# NUC973.net
KiCad netlist of a schematic drawn in Altium Designer
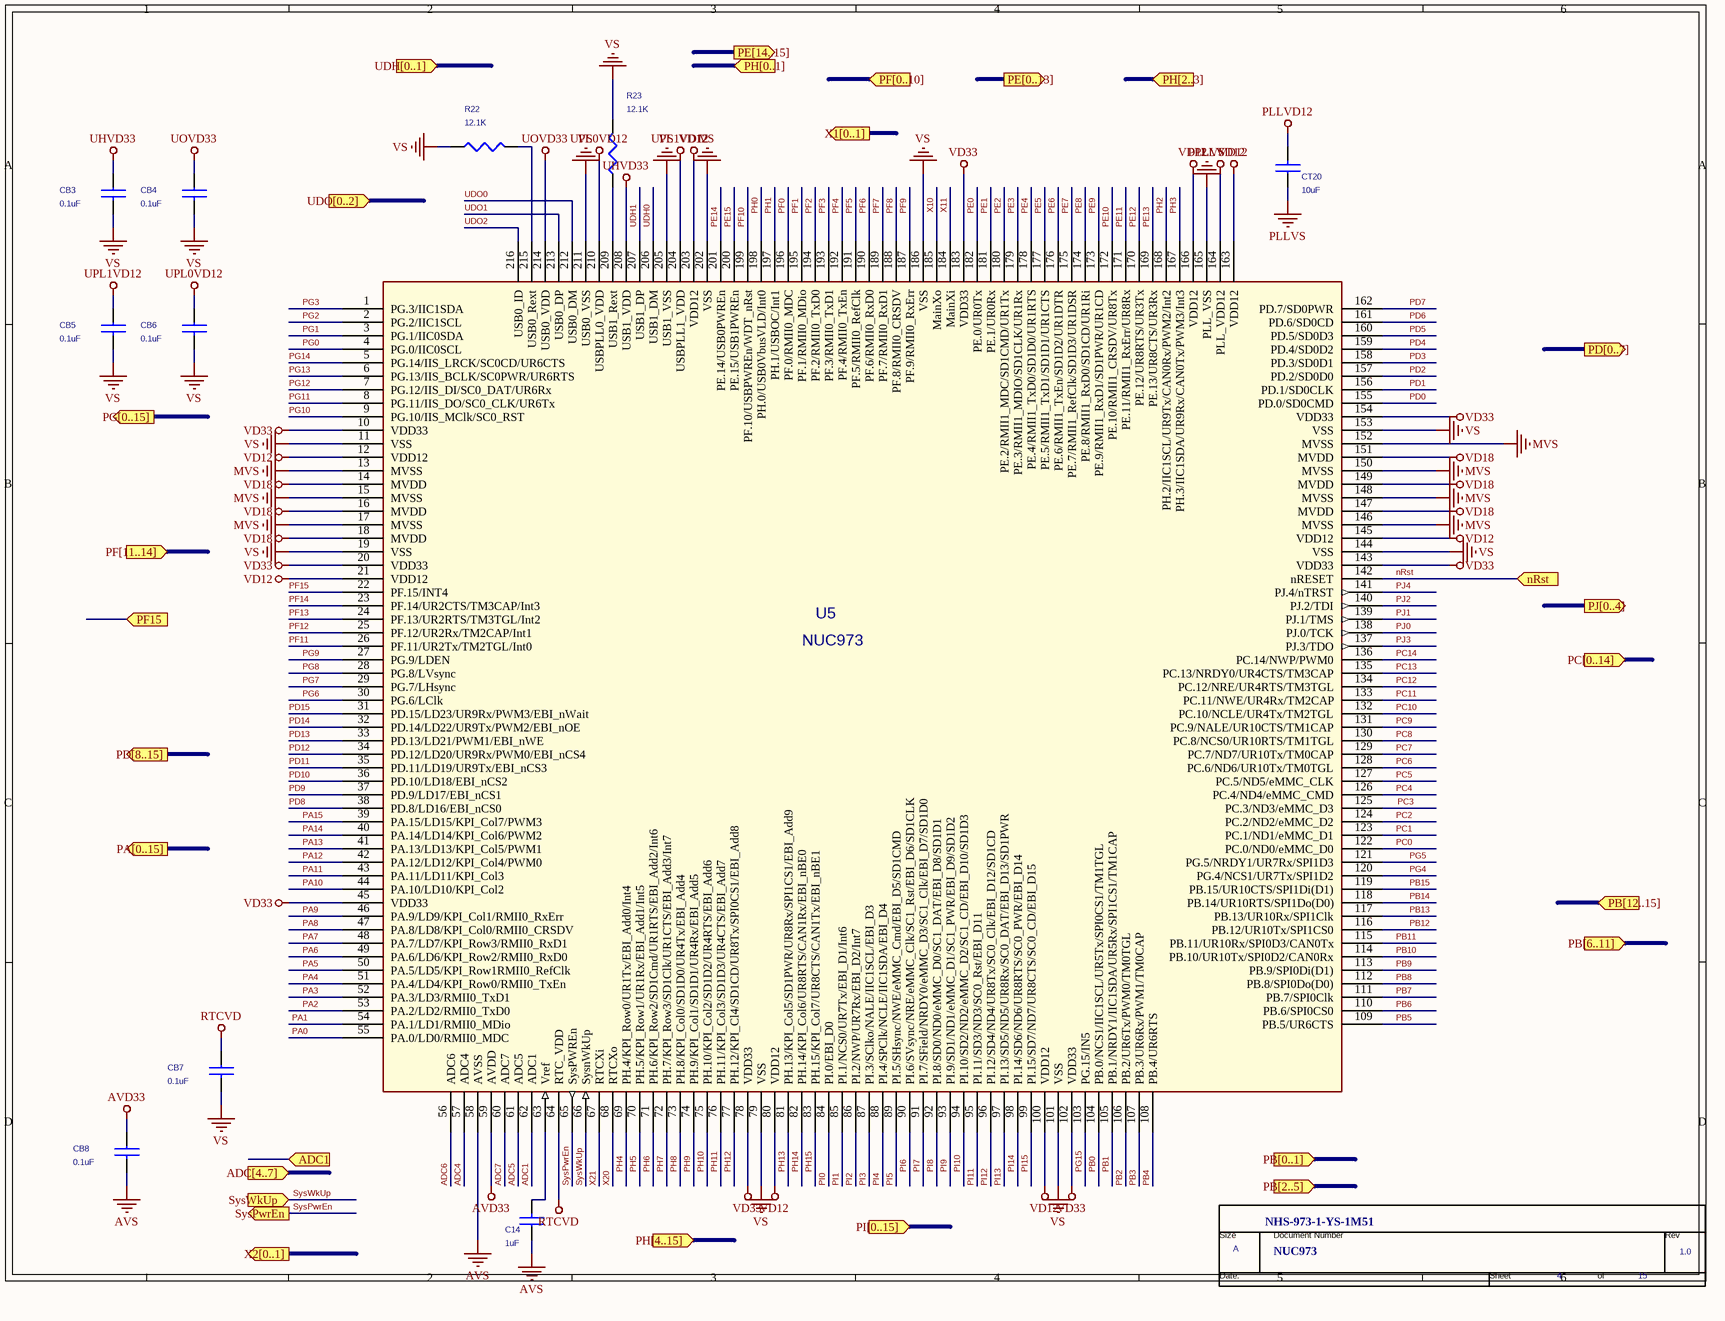
[diagram p0: NUC973.SchDoc]

(export (version "E")
  (design (tool "Eeschema 10.0.6"))
  (components
    (comp (ref "*")
      (value "TitleBlock0N")
      (fields
        (field (name "REVCODE") "1.0")
        (field (name "PAGE SIZE") "A")
        (field (name "PAGE NUMBER") "4")
        (field (name "PAGE COUNT") "15")
        (field (name "DOC") "NUC973")
        (field (name "ORGNAME") "NHS-973-1-YS-1M51")
      )
      (libsource (lib "*") (part "TitleBlock0N"))
    )
    (comp (ref "C14") (value "1uF") (footprint "C0603") (libsource (lib "*") (part "CAP NP")))
    (comp (ref "CB3") (value "0.1uF") (footprint "C0603") (libsource (lib "*") (part "CAP NP")))
    (comp (ref "CB4") (value "0.1uF") (footprint "C0603") (libsource (lib "*") (part "CAP NP")))
    (comp (ref "CB5") (value "0.1uF") (footprint "C0603") (libsource (lib "*") (part "CAP NP")))
    (comp (ref "CB6") (value "0.1uF") (footprint "C0603") (libsource (lib "*") (part "CAP NP")))
    (comp (ref "CB7") (value "0.1uF") (footprint "C0603") (libsource (lib "*") (part "CAP NP")))
    (comp (ref "CB8") (value "0.1uF") (footprint "C0603") (libsource (lib "*") (part "CAP NP")))
    (comp (ref "CT20") (value "10uF") (footprint "C0603") (libsource (lib "*") (part "CAP NP")))
    (comp (ref "R22") (value "12.1K") (footprint "R0603") (libsource (lib "*") (part "R")))
    (comp (ref "R23") (value "12.1K") (footprint "R0603") (libsource (lib "*") (part "R")))
    (comp (ref "U5") (value "NUC973") (footprint "LQFP-216") (libsource (lib "*") (part "NUC973_6")))
  )
  (nets
    (net (code "1") (name "/ADC1") (class "Default")
      (node (ref "U5") (pin "62") (pinfunction "ADC1_62") (pintype "passive"))
    )
    (net (code "2") (name "/ADC4") (class "Default")
      (node (ref "U5") (pin "57") (pinfunction "ADC4_57") (pintype "passive"))
    )
    (net (code "3") (name "/ADC5") (class "Default")
      (node (ref "U5") (pin "61") (pinfunction "ADC5_61") (pintype "passive"))
    )
    (net (code "4") (name "/ADC6") (class "Default")
      (node (ref "U5") (pin "56") (pinfunction "ADC6_56") (pintype "passive"))
    )
    (net (code "5") (name "/ADC7") (class "Default")
      (node (ref "U5") (pin "60") (pinfunction "ADC7_60") (pintype "passive"))
    )
    (net (code "7") (name "/PA0") (class "Default")
      (node (ref "U5") (pin "55") (pinfunction "PA.0/LD0/RMII0_MDC_55") (pintype "passive"))
    )
    (net (code "8") (name "/PA1") (class "Default")
      (node (ref "U5") (pin "54") (pinfunction "PA.1/LD1/RMII0_MDio_54") (pintype "passive"))
    )
    (net (code "9") (name "/PA2") (class "Default")
      (node (ref "U5") (pin "53") (pinfunction "PA.2/LD2/RMII0_TxD0_53") (pintype "passive"))
    )
    (net (code "10") (name "/PA3") (class "Default")
      (node (ref "U5") (pin "52") (pinfunction "PA.3/LD3/RMII0_TxD1_52") (pintype "passive"))
    )
    (net (code "11") (name "/PA4") (class "Default")
      (node (ref "U5") (pin "51") (pinfunction "PA.4/LD4/KPI_Row0/RMII0_TxEn_51") (pintype "passive"))
    )
    (net (code "12") (name "/PA5") (class "Default")
      (node (ref "U5") (pin "50") (pinfunction "PA.5/LD5/KPI_Row1RMII0_RefClk_50") (pintype "passive"))
    )
    (net (code "13") (name "/PA6") (class "Default")
      (node (ref "U5") (pin "49") (pinfunction "PA.6/LD6/KPI_Row2/RMII0_RxD0_49") (pintype "passive"))
    )
    (net (code "14") (name "/PA7") (class "Default")
      (node (ref "U5") (pin "48") (pinfunction "PA.7/LD7/KPI_Row3/RMII0_RxD1_48") (pintype "passive"))
    )
    (net (code "15") (name "/PA8") (class "Default")
      (node (ref "U5") (pin "47") (pinfunction "PA.8/LD8/KPI_Col0/RMII0_CRSDV_47") (pintype "passive"))
    )
    (net (code "16") (name "/PA9") (class "Default")
      (node (ref "U5") (pin "46") (pinfunction "PA.9/LD9/KPI_Col1/RMII0_RxErr_46") (pintype "passive"))
    )
    (net (code "17") (name "/PA10") (class "Default")
      (node (ref "U5") (pin "44") (pinfunction "PA.10/LD10/KPI_Col2_44") (pintype "passive"))
    )
    (net (code "18") (name "/PA11") (class "Default")
      (node (ref "U5") (pin "43") (pinfunction "PA.11/LD11/KPI_Col3_43") (pintype "passive"))
    )
    (net (code "19") (name "/PA12") (class "Default")
      (node (ref "U5") (pin "42") (pinfunction "PA.12/LD12/KPI_Col4/PWM0_42") (pintype "passive"))
    )
    (net (code "20") (name "/PA13") (class "Default")
      (node (ref "U5") (pin "41") (pinfunction "PA.13/LD13/KPI_Col5/PWM1_41") (pintype "passive"))
    )
    (net (code "21") (name "/PA14") (class "Default")
      (node (ref "U5") (pin "40") (pinfunction "PA.14/LD14/KPI_Col6/PWM2_40") (pintype "passive"))
    )
    (net (code "22") (name "/PA15") (class "Default")
      (node (ref "U5") (pin "39") (pinfunction "PA.15/LD15/KPI_Col7/PWM3_39") (pintype "passive"))
    )
    (net (code "24") (name "/PB0") (class "Default")
      (node (ref "U5") (pin "104") (pinfunction "PB.0/NCS1/IIC1SCL/UR5Tx/SPI0CS1/TM1TGL_104") (pintype "passive"))
    )
    (net (code "25") (name "/PB1") (class "Default")
      (node (ref "U5") (pin "105") (pinfunction "PB.1/NRDY1/IIC1SDA/UR5Rx/SPI1CS1/TM1CAP_105") (pintype "passive"))
    )
    (net (code "26") (name "/PB2") (class "Default")
      (node (ref "U5") (pin "106") (pinfunction "PB.2/UR6Tx/PWM0/TM0TGL_106") (pintype "passive"))
    )
    (net (code "27") (name "/PB3") (class "Default")
      (node (ref "U5") (pin "107") (pinfunction "PB.3/UR6Rx/PWM1/TM0CAP_107") (pintype "passive"))
    )
    (net (code "28") (name "/PB4") (class "Default")
      (node (ref "U5") (pin "108") (pinfunction "PB.4/UR6RTS_108") (pintype "passive"))
    )
    (net (code "29") (name "/PB5") (class "Default")
      (node (ref "U5") (pin "109") (pinfunction "PB.5/UR6CTS_109") (pintype "passive"))
    )
    (net (code "30") (name "/PB6") (class "Default")
      (node (ref "U5") (pin "110") (pinfunction "PB.6/SPI0CS0_110") (pintype "passive"))
    )
    (net (code "31") (name "/PB7") (class "Default")
      (node (ref "U5") (pin "111") (pinfunction "PB.7/SPI0Clk_111") (pintype "passive"))
    )
    (net (code "32") (name "/PB8") (class "Default")
      (node (ref "U5") (pin "112") (pinfunction "PB.8/SPI0Do(D0)_112") (pintype "passive"))
    )
    (net (code "33") (name "/PB9") (class "Default")
      (node (ref "U5") (pin "113") (pinfunction "PB.9/SPI0Di(D1)_113") (pintype "passive"))
    )
    (net (code "34") (name "/PB10") (class "Default")
      (node (ref "U5") (pin "114") (pinfunction "PB.10/UR10Tx/SPI0D2/CAN0Rx_114") (pintype "passive"))
    )
    (net (code "35") (name "/PB11") (class "Default")
      (node (ref "U5") (pin "115") (pinfunction "PB.11/UR10Rx/SPI0D3/CAN0Tx_115") (pintype "passive"))
    )
    (net (code "36") (name "/PB12") (class "Default")
      (node (ref "U5") (pin "116") (pinfunction "PB.12/UR10Tx/SPI1CS0_116") (pintype "passive"))
    )
    (net (code "37") (name "/PB13") (class "Default")
      (node (ref "U5") (pin "117") (pinfunction "PB.13/UR10Rx/SPI1Clk_117") (pintype "passive"))
    )
    (net (code "38") (name "/PB14") (class "Default")
      (node (ref "U5") (pin "118") (pinfunction "PB.14/UR10RTS/SPI1Do(D0)_118") (pintype "passive"))
    )
    (net (code "39") (name "/PB15") (class "Default")
      (node (ref "U5") (pin "119") (pinfunction "PB.15/UR10CTS/SPI1Di(D1)_119") (pintype "passive"))
    )
    (net (code "44") (name "/PC0") (class "Default")
      (node (ref "U5") (pin "122") (pinfunction "PC.0/ND0/eMMC_D0_122") (pintype "passive"))
    )
    (net (code "45") (name "/PC1") (class "Default")
      (node (ref "U5") (pin "123") (pinfunction "PC.1/ND1/eMMC_D1_123") (pintype "passive"))
    )
    (net (code "46") (name "/PC2") (class "Default")
      (node (ref "U5") (pin "124") (pinfunction "PC.2/ND2/eMMC_D2_124") (pintype "passive"))
    )
    (net (code "47") (name "/PC3") (class "Default")
      (node (ref "U5") (pin "125") (pinfunction "PC.3/ND3/eMMC_D3_125") (pintype "passive"))
    )
    (net (code "48") (name "/PC4") (class "Default")
      (node (ref "U5") (pin "126") (pinfunction "PC.4/ND4/eMMC_CMD_126") (pintype "passive"))
    )
    (net (code "49") (name "/PC5") (class "Default")
      (node (ref "U5") (pin "127") (pinfunction "PC.5/ND5/eMMC_CLK_127") (pintype "passive"))
    )
    (net (code "50") (name "/PC6") (class "Default")
      (node (ref "U5") (pin "128") (pinfunction "PC.6/ND6/UR10Tx/TM0TGL_128") (pintype "passive"))
    )
    (net (code "51") (name "/PC7") (class "Default")
      (node (ref "U5") (pin "129") (pinfunction "PC.7/ND7/UR10Tx/TM0CAP_129") (pintype "passive"))
    )
    (net (code "52") (name "/PC8") (class "Default")
      (node (ref "U5") (pin "130") (pinfunction "PC.8/NCS0/UR10RTS/TM1TGL_130") (pintype "passive"))
    )
    (net (code "53") (name "/PC9") (class "Default")
      (node (ref "U5") (pin "131") (pinfunction "PC.9/NALE/UR10CTS/TM1CAP_131") (pintype "passive"))
    )
    (net (code "54") (name "/PC10") (class "Default")
      (node (ref "U5") (pin "132") (pinfunction "PC.10/NCLE/UR4Tx/TM2TGL_132") (pintype "passive"))
    )
    (net (code "55") (name "/PC11") (class "Default")
      (node (ref "U5") (pin "133") (pinfunction "PC.11/NWE/UR4Rx/TM2CAP_133") (pintype "passive"))
    )
    (net (code "56") (name "/PC12") (class "Default")
      (node (ref "U5") (pin "134") (pinfunction "PC.12/NRE/UR4RTS/TM3TGL_134") (pintype "passive"))
    )
    (net (code "57") (name "/PC13") (class "Default")
      (node (ref "U5") (pin "135") (pinfunction "PC.13/NRDY0/UR4CTS/TM3CAP_135") (pintype "passive"))
    )
    (net (code "58") (name "/PC14") (class "Default")
      (node (ref "U5") (pin "136") (pinfunction "PC.14/NWP/PWM0_136") (pintype "passive"))
    )
    (net (code "60") (name "/PD0") (class "Default")
      (node (ref "U5") (pin "155") (pinfunction "PD.0/SD0CMD_155") (pintype "passive"))
    )
    (net (code "61") (name "/PD1") (class "Default")
      (node (ref "U5") (pin "156") (pinfunction "PD.1/SD0CLK_156") (pintype "passive"))
    )
    (net (code "62") (name "/PD2") (class "Default")
      (node (ref "U5") (pin "157") (pinfunction "PD.2/SD0D0_157") (pintype "passive"))
    )
    (net (code "63") (name "/PD3") (class "Default")
      (node (ref "U5") (pin "158") (pinfunction "PD.3/SD0D1_158") (pintype "passive"))
    )
    (net (code "64") (name "/PD4") (class "Default")
      (node (ref "U5") (pin "159") (pinfunction "PD.4/SD0D2_159") (pintype "passive"))
    )
    (net (code "65") (name "/PD5") (class "Default")
      (node (ref "U5") (pin "160") (pinfunction "PD.5/SD0D3_160") (pintype "passive"))
    )
    (net (code "66") (name "/PD6") (class "Default")
      (node (ref "U5") (pin "161") (pinfunction "PD.6/SD0CD_161") (pintype "passive"))
    )
    (net (code "67") (name "/PD7") (class "Default")
      (node (ref "U5") (pin "162") (pinfunction "PD.7/SD0PWR_162") (pintype "passive"))
    )
    (net (code "68") (name "/PD8") (class "Default")
      (node (ref "U5") (pin "38") (pinfunction "PD.8/LD16/EBI_nCS0_38") (pintype "passive"))
    )
    (net (code "69") (name "/PD9") (class "Default")
      (node (ref "U5") (pin "37") (pinfunction "PD.9/LD17/EBI_nCS1_37") (pintype "passive"))
    )
    (net (code "70") (name "/PD10") (class "Default")
      (node (ref "U5") (pin "36") (pinfunction "PD.10/LD18/EBI_nCS2_36") (pintype "passive"))
    )
    (net (code "71") (name "/PD11") (class "Default")
      (node (ref "U5") (pin "35") (pinfunction "PD.11/LD19/UR9Tx/EBI_nCS3_35") (pintype "passive"))
    )
    (net (code "72") (name "/PD12") (class "Default")
      (node (ref "U5") (pin "34") (pinfunction "PD.12/LD20/UR9Rx/PWM0/EBI_nCS4_34") (pintype "passive"))
    )
    (net (code "73") (name "/PD13") (class "Default")
      (node (ref "U5") (pin "33") (pinfunction "PD.13/LD21/PWM1/EBI_nWE_33") (pintype "passive"))
    )
    (net (code "74") (name "/PD14") (class "Default")
      (node (ref "U5") (pin "32") (pinfunction "PD.14/LD22/UR9Tx/PWM2/EBI_nOE_32") (pintype "passive"))
    )
    (net (code "75") (name "/PD15") (class "Default")
      (node (ref "U5") (pin "31") (pinfunction "PD.15/LD23/UR9Rx/PWM3/EBI_nWait_31") (pintype "passive"))
    )
    (net (code "78") (name "/PE0") (class "Default")
      (node (ref "U5") (pin "182") (pinfunction "PE.0/UR0Tx_182") (pintype "passive"))
    )
    (net (code "79") (name "/PE1") (class "Default")
      (node (ref "U5") (pin "181") (pinfunction "PE.1/UR0Rx_181") (pintype "passive"))
    )
    (net (code "80") (name "/PE2") (class "Default")
      (node (ref "U5") (pin "180") (pinfunction "PE.2/RMII1_MDC/SD1CMD/UR1Tx_180") (pintype "passive"))
    )
    (net (code "81") (name "/PE3") (class "Default")
      (node (ref "U5") (pin "179") (pinfunction "PE.3/RMII1_MDIO/SD1CLK/UR1Rx_179") (pintype "passive"))
    )
    (net (code "82") (name "/PE4") (class "Default")
      (node (ref "U5") (pin "178") (pinfunction "PE.4/RMII1_TxD0/SD1D0/UR1RTS_178") (pintype "passive"))
    )
    (net (code "83") (name "/PE5") (class "Default")
      (node (ref "U5") (pin "177") (pinfunction "PE.5/RMII1_TxD1/SD1D1/UR1CTS_177") (pintype "passive"))
    )
    (net (code "84") (name "/PE6") (class "Default")
      (node (ref "U5") (pin "176") (pinfunction "PE.6/RMII1_TxEn/SD1D2/UR1DTR_176") (pintype "passive"))
    )
    (net (code "85") (name "/PE7") (class "Default")
      (node (ref "U5") (pin "175") (pinfunction "PE.7/RMII1_RefClk/SD1D3/UR1DSR_175") (pintype "passive"))
    )
    (net (code "86") (name "/PE8") (class "Default")
      (node (ref "U5") (pin "174") (pinfunction "PE.8/RMII1_RxD0/SD1CD/UR1Ri_174") (pintype "passive"))
    )
    (net (code "87") (name "/PE9") (class "Default")
      (node (ref "U5") (pin "173") (pinfunction "PE.9/RMII1_RxD1/SD1PWR/UR1CD_173") (pintype "passive"))
    )
    (net (code "88") (name "/PE10") (class "Default")
      (node (ref "U5") (pin "172") (pinfunction "PE.10/RMII1_CRSDV/UR8Tx_172") (pintype "passive"))
    )
    (net (code "89") (name "/PE11") (class "Default")
      (node (ref "U5") (pin "171") (pinfunction "PE.11/RMII1_RxErr/UR8Rx_171") (pintype "passive"))
    )
    (net (code "90") (name "/PE12") (class "Default")
      (node (ref "U5") (pin "170") (pinfunction "PE.12/UR8RTS/UR3Tx_170") (pintype "passive"))
    )
    (net (code "91") (name "/PE13") (class "Default")
      (node (ref "U5") (pin "169") (pinfunction "PE.13/UR8CTS/UR3Rx_169") (pintype "passive"))
    )
    (net (code "92") (name "/PE14") (class "Default")
      (node (ref "U5") (pin "201") (pinfunction "PE.14/USB0PWREn_201") (pintype "passive"))
    )
    (net (code "93") (name "/PE15") (class "Default")
      (node (ref "U5") (pin "200") (pinfunction "PE.15/USB1PWREn_200") (pintype "passive"))
    )
    (net (code "96") (name "/PF0") (class "Default")
      (node (ref "U5") (pin "196") (pinfunction "PF.0/RMII0_MDC_196") (pintype "passive"))
    )
    (net (code "97") (name "/PF1") (class "Default")
      (node (ref "U5") (pin "195") (pinfunction "PF.1/RMII0_MDio_195") (pintype "passive"))
    )
    (net (code "98") (name "/PF2") (class "Default")
      (node (ref "U5") (pin "194") (pinfunction "PF.2/RMII0_TxD0_194") (pintype "passive"))
    )
    (net (code "99") (name "/PF3") (class "Default")
      (node (ref "U5") (pin "193") (pinfunction "PF.3/RMII0_TxD1_193") (pintype "passive"))
    )
    (net (code "100") (name "/PF4") (class "Default")
      (node (ref "U5") (pin "192") (pinfunction "PF.4/RMII0_TxEn_192") (pintype "passive"))
    )
    (net (code "101") (name "/PF5") (class "Default")
      (node (ref "U5") (pin "191") (pinfunction "PF.5/RMII0_RefClk_191") (pintype "passive"))
    )
    (net (code "102") (name "/PF6") (class "Default")
      (node (ref "U5") (pin "190") (pinfunction "PF.6/RMII0_RxD0_190") (pintype "passive"))
    )
    (net (code "103") (name "/PF7") (class "Default")
      (node (ref "U5") (pin "189") (pinfunction "PF.7/RMII0_RxD1_189") (pintype "passive"))
    )
    (net (code "104") (name "/PF8") (class "Default")
      (node (ref "U5") (pin "188") (pinfunction "PF.8/RMII0_CRSDV_188") (pintype "passive"))
    )
    (net (code "105") (name "/PF9") (class "Default")
      (node (ref "U5") (pin "187") (pinfunction "PF.9/RMII0_RxErr_187") (pintype "passive"))
    )
    (net (code "106") (name "/PF10") (class "Default")
      (node (ref "U5") (pin "199") (pinfunction "PF.10/USBPWREn/WDT_nRst_199") (pintype "passive"))
    )
    (net (code "107") (name "/PF11") (class "Default")
      (node (ref "U5") (pin "26") (pinfunction "PF.11/UR2Tx/TM2TGL/Int0_26") (pintype "passive"))
    )
    (net (code "108") (name "/PF12") (class "Default")
      (node (ref "U5") (pin "25") (pinfunction "PF.12/UR2Rx/TM2CAP/Int1_25") (pintype "passive"))
    )
    (net (code "109") (name "/PF13") (class "Default")
      (node (ref "U5") (pin "24") (pinfunction "PF.13/UR2RTS/TM3TGL/Int2_24") (pintype "passive"))
    )
    (net (code "110") (name "/PF14") (class "Default")
      (node (ref "U5") (pin "23") (pinfunction "PF.14/UR2CTS/TM3CAP/Int3_23") (pintype "passive"))
    )
    (net (code "111") (name "/PF15") (class "Default")
      (node (ref "U5") (pin "22") (pinfunction "PF.15/INT4_22") (pintype "passive"))
    )
    (net (code "114") (name "/PG0") (class "Default")
      (node (ref "U5") (pin "4") (pinfunction "PG.0/IIC0SCL_4") (pintype "passive"))
    )
    (net (code "115") (name "/PG1") (class "Default")
      (node (ref "U5") (pin "3") (pinfunction "PG.1/IIC0SDA_3") (pintype "passive"))
    )
    (net (code "116") (name "/PG2") (class "Default")
      (node (ref "U5") (pin "2") (pinfunction "PG.2/IIC1SCL_2") (pintype "passive"))
    )
    (net (code "117") (name "/PG3") (class "Default")
      (node (ref "U5") (pin "1") (pinfunction "PG.3/IIC1SDA_1") (pintype "passive"))
    )
    (net (code "118") (name "/PG4") (class "Default")
      (node (ref "U5") (pin "120") (pinfunction "PG.4/NCS1/UR7Tx/SPI1D2_120") (pintype "passive"))
    )
    (net (code "119") (name "/PG5") (class "Default")
      (node (ref "U5") (pin "121") (pinfunction "PG.5/NRDY1/UR7Rx/SPI1D3_121") (pintype "passive"))
    )
    (net (code "120") (name "/PG6") (class "Default")
      (node (ref "U5") (pin "30") (pinfunction "PG.6/LClk_30") (pintype "passive"))
    )
    (net (code "121") (name "/PG7") (class "Default")
      (node (ref "U5") (pin "29") (pinfunction "PG.7/LHsync_29") (pintype "passive"))
    )
    (net (code "122") (name "/PG8") (class "Default")
      (node (ref "U5") (pin "28") (pinfunction "PG.8/LVsync_28") (pintype "passive"))
    )
    (net (code "123") (name "/PG9") (class "Default")
      (node (ref "U5") (pin "27") (pinfunction "PG.9/LDEN_27") (pintype "passive"))
    )
    (net (code "124") (name "/PG10") (class "Default")
      (node (ref "U5") (pin "9") (pinfunction "PG.10/IIS_MClk/SC0_RST_9") (pintype "passive"))
    )
    (net (code "125") (name "/PG11") (class "Default")
      (node (ref "U5") (pin "8") (pinfunction "PG.11/IIS_DO/SC0_CLK/UR6Tx_8") (pintype "passive"))
    )
    (net (code "126") (name "/PG12") (class "Default")
      (node (ref "U5") (pin "7") (pinfunction "PG.12/IIS_DI/SC0_DAT/UR6Rx_7") (pintype "passive"))
    )
    (net (code "127") (name "/PG13") (class "Default")
      (node (ref "U5") (pin "6") (pinfunction "PG.13/IIS_BCLK/SC0PWR/UR6RTS_6") (pintype "passive"))
    )
    (net (code "128") (name "/PG14") (class "Default")
      (node (ref "U5") (pin "5") (pinfunction "PG.14/IIS_LRCK/SC0CD/UR6CTS_5") (pintype "passive"))
    )
    (net (code "129") (name "/PG15") (class "Default")
      (node (ref "U5") (pin "103") (pinfunction "PG.15/IN5_103") (pintype "passive"))
    )
    (net (code "131") (name "/PH0") (class "Default")
      (node (ref "U5") (pin "198") (pinfunction "PH.0/USB0VbusVLD/Int0_198") (pintype "passive"))
    )
    (net (code "132") (name "/PH1") (class "Default")
      (node (ref "U5") (pin "197") (pinfunction "PH.1/USBOC/Int1_197") (pintype "passive"))
    )
    (net (code "133") (name "/PH2") (class "Default")
      (node (ref "U5") (pin "168") (pinfunction "PH.2/IIC1SCL/UR9Tx/CAN0Rx/PWM2/Int2_168") (pintype "passive"))
    )
    (net (code "134") (name "/PH3") (class "Default")
      (node (ref "U5") (pin "167") (pinfunction "PH.3/IIC1SDA/UR9Rx/CAN0Tx/PWM3/Int3_167") (pintype "passive"))
    )
    (net (code "135") (name "/PH4") (class "Default")
      (node (ref "U5") (pin "69") (pinfunction "PH.4/KPI_Row0/UR1Tx/EBI_Add0/Int4_69") (pintype "passive"))
    )
    (net (code "136") (name "/PH5") (class "Default")
      (node (ref "U5") (pin "70") (pinfunction "PH.5/KPI_Row1/UR1Rx/EBI_Add1/Int5_70") (pintype "passive"))
    )
    (net (code "137") (name "/PH6") (class "Default")
      (node (ref "U5") (pin "71") (pinfunction "PH.6/KPI_Row2/SD1Cmd/UR1RTS/EBI_Add2/Int6_71") (pintype "passive"))
    )
    (net (code "138") (name "/PH7") (class "Default")
      (node (ref "U5") (pin "72") (pinfunction "PH.7/KPI_Row3/SD1Clk/UR1CTS/EBI_Add3/Int7_72") (pintype "passive"))
    )
    (net (code "139") (name "/PH8") (class "Default")
      (node (ref "U5") (pin "73") (pinfunction "PH.8/KPI_Col0/SD1D0/UR4Tx/EBI_Add4_73") (pintype "passive"))
    )
    (net (code "140") (name "/PH9") (class "Default")
      (node (ref "U5") (pin "74") (pinfunction "PH.9/KPI_Col1/SD1D1/UR4Rx/EBI_Add5_74") (pintype "passive"))
    )
    (net (code "141") (name "/PH10") (class "Default")
      (node (ref "U5") (pin "75") (pinfunction "PH.10/KPI_Col2/SD1D2/UR4RTS/EBI_Add6_75") (pintype "passive"))
    )
    (net (code "142") (name "/PH11") (class "Default")
      (node (ref "U5") (pin "76") (pinfunction "PH.11/KPI_Col3/SD1D3/UR4CTS/EBI_Add7_76") (pintype "passive"))
    )
    (net (code "143") (name "/PH12") (class "Default")
      (node (ref "U5") (pin "77") (pinfunction "PH.12/KPI_Cl4/SD1CD/UR8Tx/SPI0CS1/EBI_Add8_77") (pintype "passive"))
    )
    (net (code "144") (name "/PH13") (class "Default")
      (node (ref "U5") (pin "81") (pinfunction "PH.13/KPI_Col5/SD1PWR/UR8Rx/SPI1CS1/EBI_Add9_81") (pintype "passive"))
    )
    (net (code "145") (name "/PH14") (class "Default")
      (node (ref "U5") (pin "82") (pinfunction "PH.14/KPI_Col6/UR8RTS/CAN1Rx/EBI_nBE0_82") (pintype "passive"))
    )
    (net (code "146") (name "/PH15") (class "Default")
      (node (ref "U5") (pin "83") (pinfunction "PH.15/KPI_Col7/UR8CTS/CAN1Tx/EBI_nBE1_83") (pintype "passive"))
    )
    (net (code "150") (name "/PI0") (class "Default")
      (node (ref "U5") (pin "84") (pinfunction "PI.0/EBI_D0_84") (pintype "passive"))
    )
    (net (code "151") (name "/PI1") (class "Default")
      (node (ref "U5") (pin "85") (pinfunction "PI.1/NCS0/UR7Tx/EBI_D1/Int6_85") (pintype "passive"))
    )
    (net (code "152") (name "/PI2") (class "Default")
      (node (ref "U5") (pin "86") (pinfunction "PI.2/NWP/UR7Rx/EBI_D2/Int7_86") (pintype "passive"))
    )
    (net (code "153") (name "/PI3") (class "Default")
      (node (ref "U5") (pin "87") (pinfunction "PI.3/SClko/NALE/IIC1SCL/EBI_D3_87") (pintype "passive"))
    )
    (net (code "154") (name "/PI4") (class "Default")
      (node (ref "U5") (pin "88") (pinfunction "PI.4/SPClk/NCLE/IIC1SDA/EBI_D4_88") (pintype "passive"))
    )
    (net (code "155") (name "/PI5") (class "Default")
      (node (ref "U5") (pin "89") (pinfunction "PI.5/SHsync/NWE/eMMC_Cmd/EBI_D5/SD1CMD_89") (pintype "passive"))
    )
    (net (code "156") (name "/PI6") (class "Default")
      (node (ref "U5") (pin "90") (pinfunction "PI.6/SVsync/NRE/eMMC_Clk/SC1_Rst/EBI_D6/SD1CLK_90") (pintype "passive"))
    )
    (net (code "157") (name "/PI7") (class "Default")
      (node (ref "U5") (pin "91") (pinfunction "PI.7/SField/NRDY0/eMMC_D3/SC1_Clk/EBI_D7/SD1D0_91") (pintype "passive"))
    )
    (net (code "158") (name "/PI8") (class "Default")
      (node (ref "U5") (pin "92") (pinfunction "PI.8/SD0/ND0/eMMC_D0/SC1_DAT/EBI_D8/SD1D1_92") (pintype "passive"))
    )
    (net (code "159") (name "/PI9") (class "Default")
      (node (ref "U5") (pin "93") (pinfunction "PI.9/SD1/ND1/eMMC_D1/SC1_PWR/EBI_D9/SD1D2_93") (pintype "passive"))
    )
    (net (code "160") (name "/PI10") (class "Default")
      (node (ref "U5") (pin "94") (pinfunction "PI.10/SD2/ND2/eMMC_D2/SC1_CD/EBI_D10/SD1D3_94") (pintype "passive"))
    )
    (net (code "161") (name "/PI11") (class "Default")
      (node (ref "U5") (pin "95") (pinfunction "PI.11/SD3/ND3/SC0_Rst/EBI_D11_95") (pintype "passive"))
    )
    (net (code "162") (name "/PI12") (class "Default")
      (node (ref "U5") (pin "96") (pinfunction "PI.12/SD4/ND4/UR8Tx/SC0_Clk/EBI_D12/SD1CD_96") (pintype "passive"))
    )
    (net (code "163") (name "/PI13") (class "Default")
      (node (ref "U5") (pin "97") (pinfunction "PI.13/SD5/ND5/UR8Rx/SC0_DAT/EBI_D13/SD1PWR_97") (pintype "passive"))
    )
    (net (code "164") (name "/PI14") (class "Default")
      (node (ref "U5") (pin "98") (pinfunction "PI.14/SD6/ND6/UR8RTS/SC0_PWR/EBI_D14_98") (pintype "passive"))
    )
    (net (code "165") (name "/PI15") (class "Default")
      (node (ref "U5") (pin "99") (pinfunction "PI.15/SD7/ND7/UR8CTS/SC0_CD/EBI_D15_99") (pintype "passive"))
    )
    (net (code "167") (name "/PJ0") (class "Default")
      (node (ref "U5") (pin "138") (pinfunction "PJ.0/TCK_138") (pintype "output"))
    )
    (net (code "168") (name "/PJ1") (class "Default")
      (node (ref "U5") (pin "139") (pinfunction "PJ.1/TMS_139") (pintype "output"))
    )
    (net (code "169") (name "/PJ2") (class "Default")
      (node (ref "U5") (pin "140") (pinfunction "PJ.2/TDI_140") (pintype "output"))
    )
    (net (code "170") (name "/PJ3") (class "Default")
      (node (ref "U5") (pin "137") (pinfunction "PJ.3/TDO_137") (pintype "output"))
    )
    (net (code "171") (name "/PJ4") (class "Default")
      (node (ref "U5") (pin "141") (pinfunction "PJ.4/nTRST_141") (pintype "output"))
    )
    (net (code "173") (name "/SysPwrEn") (class "Default")
      (node (ref "U5") (pin "65") (pinfunction "SysPWREn_65") (pintype "output"))
    )
    (net (code "174") (name "/SysWkUp") (class "Default")
      (node (ref "U5") (pin "66") (pinfunction "SysnWkUp_66") (pintype "input"))
    )
    (net (code "175") (name "/UDH0") (class "Default")
      (node (ref "U5") (pin "206") (pinfunction "USB1_DM_206") (pintype "passive"))
    )
    (net (code "176") (name "/UDH1") (class "Default")
      (node (ref "U5") (pin "207") (pinfunction "USB1_DP_207") (pintype "passive"))
    )
    (net (code "178") (name "/UDO0") (class "Default")
      (node (ref "U5") (pin "212") (pinfunction "USB0_DM_212") (pintype "passive"))
    )
    (net (code "179") (name "/UDO1") (class "Default")
      (node (ref "U5") (pin "213") (pinfunction "USB0_DP_213") (pintype "passive"))
    )
    (net (code "180") (name "/UDO2") (class "Default")
      (node (ref "U5") (pin "216") (pinfunction "USB0_ID_216") (pintype "passive"))
    )
    (net (code "184") (name "/X10") (class "Default")
      (node (ref "U5") (pin "185") (pinfunction "MainXo_185") (pintype "passive"))
    )
    (net (code "185") (name "/X11") (class "Default")
      (node (ref "U5") (pin "184") (pinfunction "MainXi_184") (pintype "passive"))
    )
    (net (code "186") (name "/X20") (class "Default")
      (node (ref "U5") (pin "68") (pinfunction "RTCXo_68") (pintype "passive"))
    )
    (net (code "187") (name "/X21") (class "Default")
      (node (ref "U5") (pin "67") (pinfunction "RTCXi_67") (pintype "passive"))
    )
    (net (code "188") (name "/nRst") (class "Default")
      (node (ref "U5") (pin "142") (pinfunction "nRESET_142") (pintype "passive"))
    )
    (net (code "189") (name "AVD33") (class "Default")
      (node (ref "CB8") (pin "1") (pinfunction "1_1") (pintype "passive"))
      (node (ref "U5") (pin "59") (pinfunction "AVDD_59") (pintype "passive"))
    )
    (net (code "190") (name "AVS") (class "Default")
      (node (ref "C14") (pin "1") (pinfunction "1_1") (pintype "passive"))
      (node (ref "CB8") (pin "2") (pinfunction "2_2") (pintype "passive"))
      (node (ref "U5") (pin "58") (pinfunction "AVSS_58") (pintype "passive"))
    )
    (net (code "191") (name "MVS") (class "Default")
      (node (ref "U5") (pin "13") (pinfunction "MVSS_13") (pintype "power_in"))
      (node (ref "U5") (pin "146") (pinfunction "MVSS_146") (pintype "power_in"))
      (node (ref "U5") (pin "148") (pinfunction "MVSS_148") (pintype "power_in"))
      (node (ref "U5") (pin "15") (pinfunction "MVSS_15") (pintype "power_in"))
      (node (ref "U5") (pin "150") (pinfunction "MVSS_150") (pintype "power_in"))
      (node (ref "U5") (pin "152") (pinfunction "MVSS_152") (pintype "power_in"))
      (node (ref "U5") (pin "17") (pinfunction "MVSS_17") (pintype "power_in"))
    )
    (net (code "192") (name "Net-(U5-USB0_Rext)") (class "Default")
      (node (ref "R22") (pin "1") (pinfunction "1_1") (pintype "passive"))
      (node (ref "U5") (pin "215") (pinfunction "USB0_Rext_215") (pintype "passive"))
    )
    (net (code "193") (name "Net-(U5-USB1_Rext)") (class "Default")
      (node (ref "R23") (pin "1") (pinfunction "1_1") (pintype "passive"))
      (node (ref "U5") (pin "209") (pinfunction "USB1_Rext_209") (pintype "passive"))
    )
    (net (code "194") (name "Net-(U5-Vref)") (class "Default")
      (node (ref "C14") (pin "2") (pinfunction "2_2") (pintype "passive"))
      (node (ref "U5") (pin "63") (pinfunction "Vref_63") (pintype "input"))
    )
    (net (code "195") (name "PLLVD12") (class "Default")
      (node (ref "CT20") (pin "2") (pinfunction "2_2") (pintype "passive"))
      (node (ref "U5") (pin "164") (pinfunction "PLL_VDD12_164") (pintype "power_in"))
    )
    (net (code "196") (name "PLLVS") (class "Default")
      (node (ref "CT20") (pin "1") (pinfunction "1_1") (pintype "passive"))
      (node (ref "U5") (pin "165") (pinfunction "PLL_VSS_165") (pintype "power_in"))
    )
    (net (code "197") (name "RTCVD") (class "Default")
      (node (ref "CB7") (pin "1") (pinfunction "1_1") (pintype "passive"))
      (node (ref "U5") (pin "64") (pinfunction "RTC_VDD_64") (pintype "power_in"))
    )
    (net (code "198") (name "UHVD33") (class "Default")
      (node (ref "CB3") (pin "1") (pinfunction "1_1") (pintype "passive"))
      (node (ref "U5") (pin "208") (pinfunction "USB1_VDD_208") (pintype "power_in"))
    )
    (net (code "199") (name "UOVD33") (class "Default")
      (node (ref "CB4") (pin "1") (pinfunction "1_1") (pintype "passive"))
      (node (ref "U5") (pin "214") (pinfunction "USB0_VDD_214") (pintype "power_in"))
    )
    (net (code "200") (name "UPL0VD12") (class "Default")
      (node (ref "CB6") (pin "1") (pinfunction "1_1") (pintype "passive"))
      (node (ref "U5") (pin "210") (pinfunction "USBPLL0_VDD_210") (pintype "power_in"))
    )
    (net (code "201") (name "UPL1VD12") (class "Default")
      (node (ref "CB5") (pin "1") (pinfunction "1_1") (pintype "passive"))
      (node (ref "U5") (pin "204") (pinfunction "USBPLL1_VDD_204") (pintype "power_in"))
    )
    (net (code "202") (name "VD12") (class "Default")
      (node (ref "U5") (pin "100") (pinfunction "VDD12_100") (pintype "power_in"))
      (node (ref "U5") (pin "12") (pinfunction "VDD12_12") (pintype "power_in"))
      (node (ref "U5") (pin "145") (pinfunction "VDD12_145") (pintype "power_in"))
      (node (ref "U5") (pin "163") (pinfunction "VDD12_163") (pintype "power_in"))
      (node (ref "U5") (pin "166") (pinfunction "VDD12_166") (pintype "power_in"))
      (node (ref "U5") (pin "203") (pinfunction "VDD12_203") (pintype "power_in"))
      (node (ref "U5") (pin "21") (pinfunction "VDD12_21") (pintype "power_in"))
      (node (ref "U5") (pin "80") (pinfunction "VDD12_80") (pintype "power_in"))
    )
    (net (code "203") (name "VD18") (class "Default")
      (node (ref "U5") (pin "14") (pinfunction "MVDD_14") (pintype "power_in"))
      (node (ref "U5") (pin "147") (pinfunction "MVDD_147") (pintype "power_in"))
      (node (ref "U5") (pin "149") (pinfunction "MVDD_149") (pintype "power_in"))
      (node (ref "U5") (pin "151") (pinfunction "MVDD_151") (pintype "power_in"))
      (node (ref "U5") (pin "16") (pinfunction "MVDD_16") (pintype "power_in"))
      (node (ref "U5") (pin "18") (pinfunction "MVDD_18") (pintype "power_in"))
    )
    (net (code "204") (name "VD33") (class "Default")
      (node (ref "U5") (pin "10") (pinfunction "VDD33_10") (pintype "power_in"))
      (node (ref "U5") (pin "102") (pinfunction "VDD33_102") (pintype "power_in"))
      (node (ref "U5") (pin "143") (pinfunction "VDD33_143") (pintype "power_in"))
      (node (ref "U5") (pin "154") (pinfunction "VDD33_154") (pintype "power_in"))
      (node (ref "U5") (pin "183") (pinfunction "VDD33_183") (pintype "power_in"))
      (node (ref "U5") (pin "20") (pinfunction "VDD33_20") (pintype "power_in"))
      (node (ref "U5") (pin "45") (pinfunction "VDD33_45") (pintype "power_in"))
      (node (ref "U5") (pin "78") (pinfunction "VDD33_78") (pintype "power_in"))
    )
    (net (code "205") (name "VS") (class "Default")
      (node (ref "CB3") (pin "2") (pinfunction "2_2") (pintype "passive"))
      (node (ref "CB4") (pin "2") (pinfunction "2_2") (pintype "passive"))
      (node (ref "CB5") (pin "2") (pinfunction "2_2") (pintype "passive"))
      (node (ref "CB6") (pin "2") (pinfunction "2_2") (pintype "passive"))
      (node (ref "CB7") (pin "2") (pinfunction "2_2") (pintype "passive"))
      (node (ref "R22") (pin "2") (pinfunction "2_2") (pintype "passive"))
      (node (ref "R23") (pin "2") (pinfunction "2_2") (pintype "passive"))
      (node (ref "U5") (pin "101") (pinfunction "VSS_101") (pintype "power_in"))
      (node (ref "U5") (pin "11") (pinfunction "VSS_11") (pintype "power_in"))
      (node (ref "U5") (pin "144") (pinfunction "VSS_144") (pintype "power_in"))
      (node (ref "U5") (pin "153") (pinfunction "VSS_153") (pintype "power_in"))
      (node (ref "U5") (pin "186") (pinfunction "VSS_186") (pintype "power_in"))
      (node (ref "U5") (pin "19") (pinfunction "VSS_19") (pintype "power_in"))
      (node (ref "U5") (pin "202") (pinfunction "VSS_202") (pintype "power_in"))
      (node (ref "U5") (pin "205") (pinfunction "USB1_VSS_205") (pintype "power_in"))
      (node (ref "U5") (pin "211") (pinfunction "USB0_VSS_211") (pintype "passive"))
      (node (ref "U5") (pin "79") (pinfunction "VSS_79") (pintype "power_in"))
    )
  )
)
